# 2020-04-02-04-30101_-_ETC_Interface_Circ.net
KiCad netlist of a schematic drawn in Altium Designer
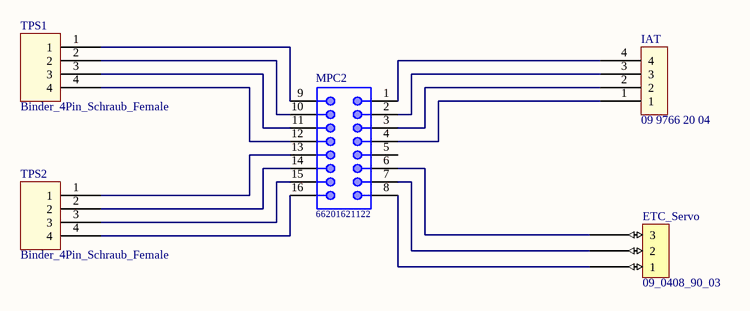
[diagram p0: 2020-04-02-04-30101 - ETC_Interface_Circuit_2.SchDoc]

(export (version "E")
  (design (tool "Eeschema 10.0.6"))
  (components
    (comp (ref "ETC_Servo")
      (value "09_0408_90_03")
      (footprint "09_0408_90_03")
      (libsource (lib "Nico_Lib") (part "09_0408_90_03"))
    )
    (comp (ref "IAT")
      (value "09 9766 20 04")
      (footprint "09 9766 20 04")
      (description "Binder 4 Pin Female SnapIn")
      (libsource (lib "Eric") (part "09 9766 20 04"))
    )
    (comp (ref "MPC2")
      (value "66201621122")
      (footprint "66201621122")
      (description "THT Male Header WR-MPC3, Vertical, Dual Row, pitch 3 mm, 16 pins")
      (fields (field (name "PUBLISHER") "Wurth Elektronik"))
      (libsource (lib "66202421122_Altium_WR-MPC3_rev18b") (part "66201621122"))
    )
    (comp (ref "TPS1")
      (value "Binder_4Pin_Schraub_Female")
      (footprint "09 0412 30 04")
      (libsource (lib "Eric") (part "Binder_4Pin_Schraub_Female"))
    )
    (comp (ref "TPS2")
      (value "Binder_4Pin_Schraub_Female")
      (footprint "09 0412 30 04")
      (libsource (lib "Eric") (part "Binder_4Pin_Schraub_Female"))
    )
  )
  (nets
    (net (code "1") (name "Net-(ETC_Servo-Pad1)") (class "Default")
      (node (ref "ETC_Servo") (pin "1") (pinfunction "1_1") (pintype "bidirectional"))
      (node (ref "MPC2") (pin "8") (pinfunction "8_8") (pintype "passive"))
    )
    (net (code "2") (name "Net-(ETC_Servo-Pad2)") (class "Default")
      (node (ref "ETC_Servo") (pin "2") (pinfunction "2_2") (pintype "bidirectional"))
      (node (ref "MPC2") (pin "7") (pinfunction "7_7") (pintype "passive"))
    )
    (net (code "3") (name "Net-(ETC_Servo-Pad3)") (class "Default")
      (node (ref "ETC_Servo") (pin "3") (pinfunction "3_3") (pintype "bidirectional"))
      (node (ref "MPC2") (pin "6") (pinfunction "6_6") (pintype "passive"))
    )
    (net (code "4") (name "Net-(IAT-Pad1)") (class "Default")
      (node (ref "IAT") (pin "1") (pinfunction "1_1") (pintype "passive"))
      (node (ref "MPC2") (pin "4") (pinfunction "4_4") (pintype "passive"))
    )
    (net (code "5") (name "Net-(IAT-Pad2)") (class "Default")
      (node (ref "IAT") (pin "2") (pinfunction "2_2") (pintype "passive"))
      (node (ref "MPC2") (pin "3") (pinfunction "3_3") (pintype "passive"))
    )
    (net (code "6") (name "Net-(IAT-Pad3)") (class "Default")
      (node (ref "IAT") (pin "3") (pinfunction "3_3") (pintype "passive"))
      (node (ref "MPC2") (pin "2") (pinfunction "2_2") (pintype "passive"))
    )
    (net (code "7") (name "Net-(IAT-Pad4)") (class "Default")
      (node (ref "IAT") (pin "4") (pinfunction "4_4") (pintype "passive"))
      (node (ref "MPC2") (pin "1") (pinfunction "1_1") (pintype "passive"))
    )
    (net (code "8") (name "Net-(MPC2-Pad9)") (class "Default")
      (node (ref "MPC2") (pin "9") (pinfunction "9_9") (pintype "passive"))
      (node (ref "TPS1") (pin "1") (pinfunction "1_1") (pintype "passive"))
    )
    (net (code "9") (name "Net-(MPC2-Pad10)") (class "Default")
      (node (ref "MPC2") (pin "10") (pinfunction "10_10") (pintype "passive"))
      (node (ref "TPS1") (pin "2") (pinfunction "2_2") (pintype "passive"))
    )
    (net (code "10") (name "Net-(MPC2-Pad11)") (class "Default")
      (node (ref "MPC2") (pin "11") (pinfunction "11_11") (pintype "passive"))
      (node (ref "TPS1") (pin "3") (pinfunction "3_3") (pintype "passive"))
    )
    (net (code "11") (name "Net-(MPC2-Pad12)") (class "Default")
      (node (ref "MPC2") (pin "12") (pinfunction "12_12") (pintype "passive"))
      (node (ref "TPS1") (pin "4") (pinfunction "4_4") (pintype "passive"))
    )
    (net (code "12") (name "Net-(MPC2-Pad13)") (class "Default")
      (node (ref "MPC2") (pin "13") (pinfunction "13_13") (pintype "passive"))
      (node (ref "TPS2") (pin "1") (pinfunction "1_1") (pintype "passive"))
    )
    (net (code "13") (name "Net-(MPC2-Pad14)") (class "Default")
      (node (ref "MPC2") (pin "14") (pinfunction "14_14") (pintype "passive"))
      (node (ref "TPS2") (pin "2") (pinfunction "2_2") (pintype "passive"))
    )
    (net (code "14") (name "Net-(MPC2-Pad15)") (class "Default")
      (node (ref "MPC2") (pin "15") (pinfunction "15_15") (pintype "passive"))
      (node (ref "TPS2") (pin "3") (pinfunction "3_3") (pintype "passive"))
    )
    (net (code "15") (name "Net-(MPC2-Pad16)") (class "Default")
      (node (ref "MPC2") (pin "16") (pinfunction "16_16") (pintype "passive"))
      (node (ref "TPS2") (pin "4") (pinfunction "4_4") (pintype "passive"))
    )
    (net (code "16") (name "unconnected-(MPC2-Pad5)") (class "Default")
      (node (ref "MPC2") (pin "5") (pinfunction "5_5") (pintype "passive"))
    )
  )
)
